# POS.net
KiCad netlist of a schematic drawn in Altium Designer
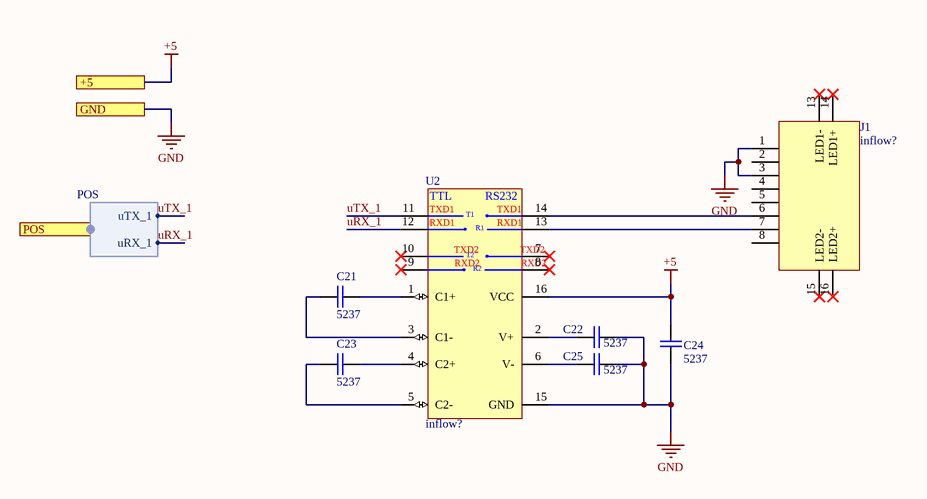
[diagram p0: POS.SchDoc]

(export (version "E")
  (design (tool "Eeschema 10.0.6"))
  (components
    (comp (ref "C21")
      (value "1u'F, 50'V")
      (footprint "CAP 1206/3216")
      (description "Bipolar ceramic capacitor SMD")
      (fields (field (name "INFLOW") "5237") (field (name "VALIDATION") "Valid"))
      (libsource (lib "aKaReZa") (part "Cap_Multi_1u_50_1206"))
    )
    (comp (ref "C22")
      (value "1u'F, 50'V")
      (footprint "CAP 1206/3216")
      (description "Bipolar ceramic capacitor SMD")
      (fields (field (name "INFLOW") "5237") (field (name "VALIDATION") "Valid"))
      (libsource (lib "aKaReZa") (part "Cap_Multi_1u_50_1206"))
    )
    (comp (ref "C23")
      (value "1u'F, 50'V")
      (footprint "CAP 1206/3216")
      (description "Bipolar ceramic capacitor SMD")
      (fields (field (name "INFLOW") "5237") (field (name "VALIDATION") "Valid"))
      (libsource (lib "aKaReZa") (part "Cap_Multi_1u_50_1206"))
    )
    (comp (ref "C24")
      (value "1u'F, 50'V")
      (footprint "CAP 1206/3216")
      (description "Bipolar ceramic capacitor SMD")
      (fields (field (name "INFLOW") "5237") (field (name "VALIDATION") "Valid"))
      (libsource (lib "aKaReZa") (part "Cap_Multi_1u_50_1206"))
    )
    (comp (ref "C25")
      (value "1u'F, 50'V")
      (footprint "CAP 1206/3216")
      (description "Bipolar ceramic capacitor SMD")
      (fields (field (name "INFLOW") "5237") (field (name "VALIDATION") "Valid"))
      (libsource (lib "aKaReZa") (part "Cap_Multi_1u_50_1206"))
    )
    (comp (ref "J1")
      (value "RJ45, mini")
      (footprint "RJ45_MINI")
      (description "RJ45 Mini With two LEDs")
      (fields (field (name "INFLOW") "inflow?") (field (name "VALIDATION") "NT"))
      (libsource (lib "aKaReZa") (part "Con_PC_RJ45_MINI"))
    )
    (comp (ref "U2")
      (value "MAX3232")
      (footprint "NSO16_M")
      (fields (field (name "INFLOW") "inflow?") (field (name "VALIDATION") "Valid"))
      (libsource (lib "vending-pad-002") (part "IC_Converter_MAX3232CSE"))
    )
  )
  (nets
    (net (code "2") (name "+5") (class "Default")
      (node (ref "C24") (pin "1") (pinfunction "1_1") (pintype "passive"))
      (node (ref "U2") (pin "16") (pinfunction "VCC_16") (pintype "power_in"))
    )
    (net (code "3") (name "/uRX_1") (class "Default")
      (node (ref "U2") (pin "12") (pinfunction "R1OUT_12") (pintype "passive"))
    )
    (net (code "4") (name "/uTX_1") (class "Default")
      (node (ref "U2") (pin "11") (pinfunction "T1IN_11") (pintype "passive"))
    )
    (net (code "6") (name "GND") (class "Default")
      (node (ref "C22") (pin "2") (pinfunction "2_2") (pintype "passive"))
      (node (ref "C24") (pin "2") (pinfunction "2_2") (pintype "passive"))
      (node (ref "C25") (pin "2") (pinfunction "2_2") (pintype "passive"))
      (node (ref "J1") (pin "1") (pintype "passive"))
      (node (ref "J1") (pin "3") (pintype "passive"))
      (node (ref "U2") (pin "15") (pinfunction "GND_15") (pintype "power_in"))
    )
    (net (code "7") (name "Net-(U2-C1+)") (class "Default")
      (node (ref "C21") (pin "1") (pinfunction "1_1") (pintype "passive"))
      (node (ref "U2") (pin "1") (pinfunction "C1+_1") (pintype "bidirectional"))
    )
    (net (code "8") (name "Net-(U2-C1-)") (class "Default")
      (node (ref "C21") (pin "2") (pinfunction "2_2") (pintype "passive"))
      (node (ref "U2") (pin "3") (pinfunction "C1-_3") (pintype "bidirectional"))
    )
    (net (code "9") (name "Net-(U2-C2+)") (class "Default")
      (node (ref "C23") (pin "1") (pinfunction "1_1") (pintype "passive"))
      (node (ref "U2") (pin "4") (pinfunction "C2+_4") (pintype "bidirectional"))
    )
    (net (code "10") (name "Net-(U2-C2-)") (class "Default")
      (node (ref "C23") (pin "2") (pinfunction "2_2") (pintype "passive"))
      (node (ref "U2") (pin "5") (pinfunction "C2-_5") (pintype "bidirectional"))
    )
    (net (code "11") (name "Net-(U2-R1IN)") (class "Default")
      (node (ref "J1") (pin "7") (pintype "passive"))
      (node (ref "U2") (pin "13") (pinfunction "R1IN_13") (pintype "passive"))
    )
    (net (code "12") (name "Net-(U2-T1OUT)") (class "Default")
      (node (ref "J1") (pin "6") (pintype "passive"))
      (node (ref "U2") (pin "14") (pinfunction "T1OUT_14") (pintype "passive"))
    )
    (net (code "13") (name "Net-(U2-V+)") (class "Default")
      (node (ref "C22") (pin "1") (pinfunction "1_1") (pintype "passive"))
      (node (ref "U2") (pin "2") (pinfunction "V+_2") (pintype "power_in"))
    )
    (net (code "14") (name "Net-(U2-V-)") (class "Default")
      (node (ref "C25") (pin "1") (pinfunction "1_1") (pintype "passive"))
      (node (ref "U2") (pin "6") (pinfunction "V-_6") (pintype "power_in"))
    )
    (net (code "15") (name "unconnected-(J1-LED1+-Pad14)") (class "Default")
      (node (ref "J1") (pin "14") (pinfunction "LED1+_14") (pintype "passive+no_connect"))
    )
    (net (code "16") (name "unconnected-(J1-LED1--Pad13)") (class "Default")
      (node (ref "J1") (pin "13") (pinfunction "LED1-_13") (pintype "passive+no_connect"))
    )
    (net (code "17") (name "unconnected-(J1-LED2+-Pad16)") (class "Default")
      (node (ref "J1") (pin "16") (pinfunction "LED2+_16") (pintype "passive+no_connect"))
    )
    (net (code "18") (name "unconnected-(J1-LED2--Pad15)") (class "Default")
      (node (ref "J1") (pin "15") (pinfunction "LED2-_15") (pintype "passive+no_connect"))
    )
    (net (code "19") (name "unconnected-(J1-Pad2)") (class "Default")
      (node (ref "J1") (pin "2") (pintype "passive"))
    )
    (net (code "20") (name "unconnected-(J1-Pad4)") (class "Default")
      (node (ref "J1") (pin "4") (pintype "passive"))
    )
    (net (code "21") (name "unconnected-(J1-Pad5)") (class "Default")
      (node (ref "J1") (pin "5") (pintype "passive"))
    )
    (net (code "22") (name "unconnected-(J1-Pad8)") (class "Default")
      (node (ref "J1") (pin "8") (pintype "passive"))
    )
    (net (code "23") (name "unconnected-(U2-R2IN-Pad8)") (class "Default")
      (node (ref "U2") (pin "8") (pinfunction "R2IN_8") (pintype "passive+no_connect"))
    )
    (net (code "24") (name "unconnected-(U2-R2OUT-Pad9)") (class "Default")
      (node (ref "U2") (pin "9") (pinfunction "R2OUT_9") (pintype "passive+no_connect"))
    )
    (net (code "25") (name "unconnected-(U2-T2IN-Pad10)") (class "Default")
      (node (ref "U2") (pin "10") (pinfunction "T2IN_10") (pintype "passive+no_connect"))
    )
    (net (code "26") (name "unconnected-(U2-T2OUT-Pad7)") (class "Default")
      (node (ref "U2") (pin "7") (pinfunction "T2OUT_7") (pintype "passive+no_connect"))
    )
  )
)
